# lin_usb_probe.net
KiCad netlist of a schematic drawn in EAGLE
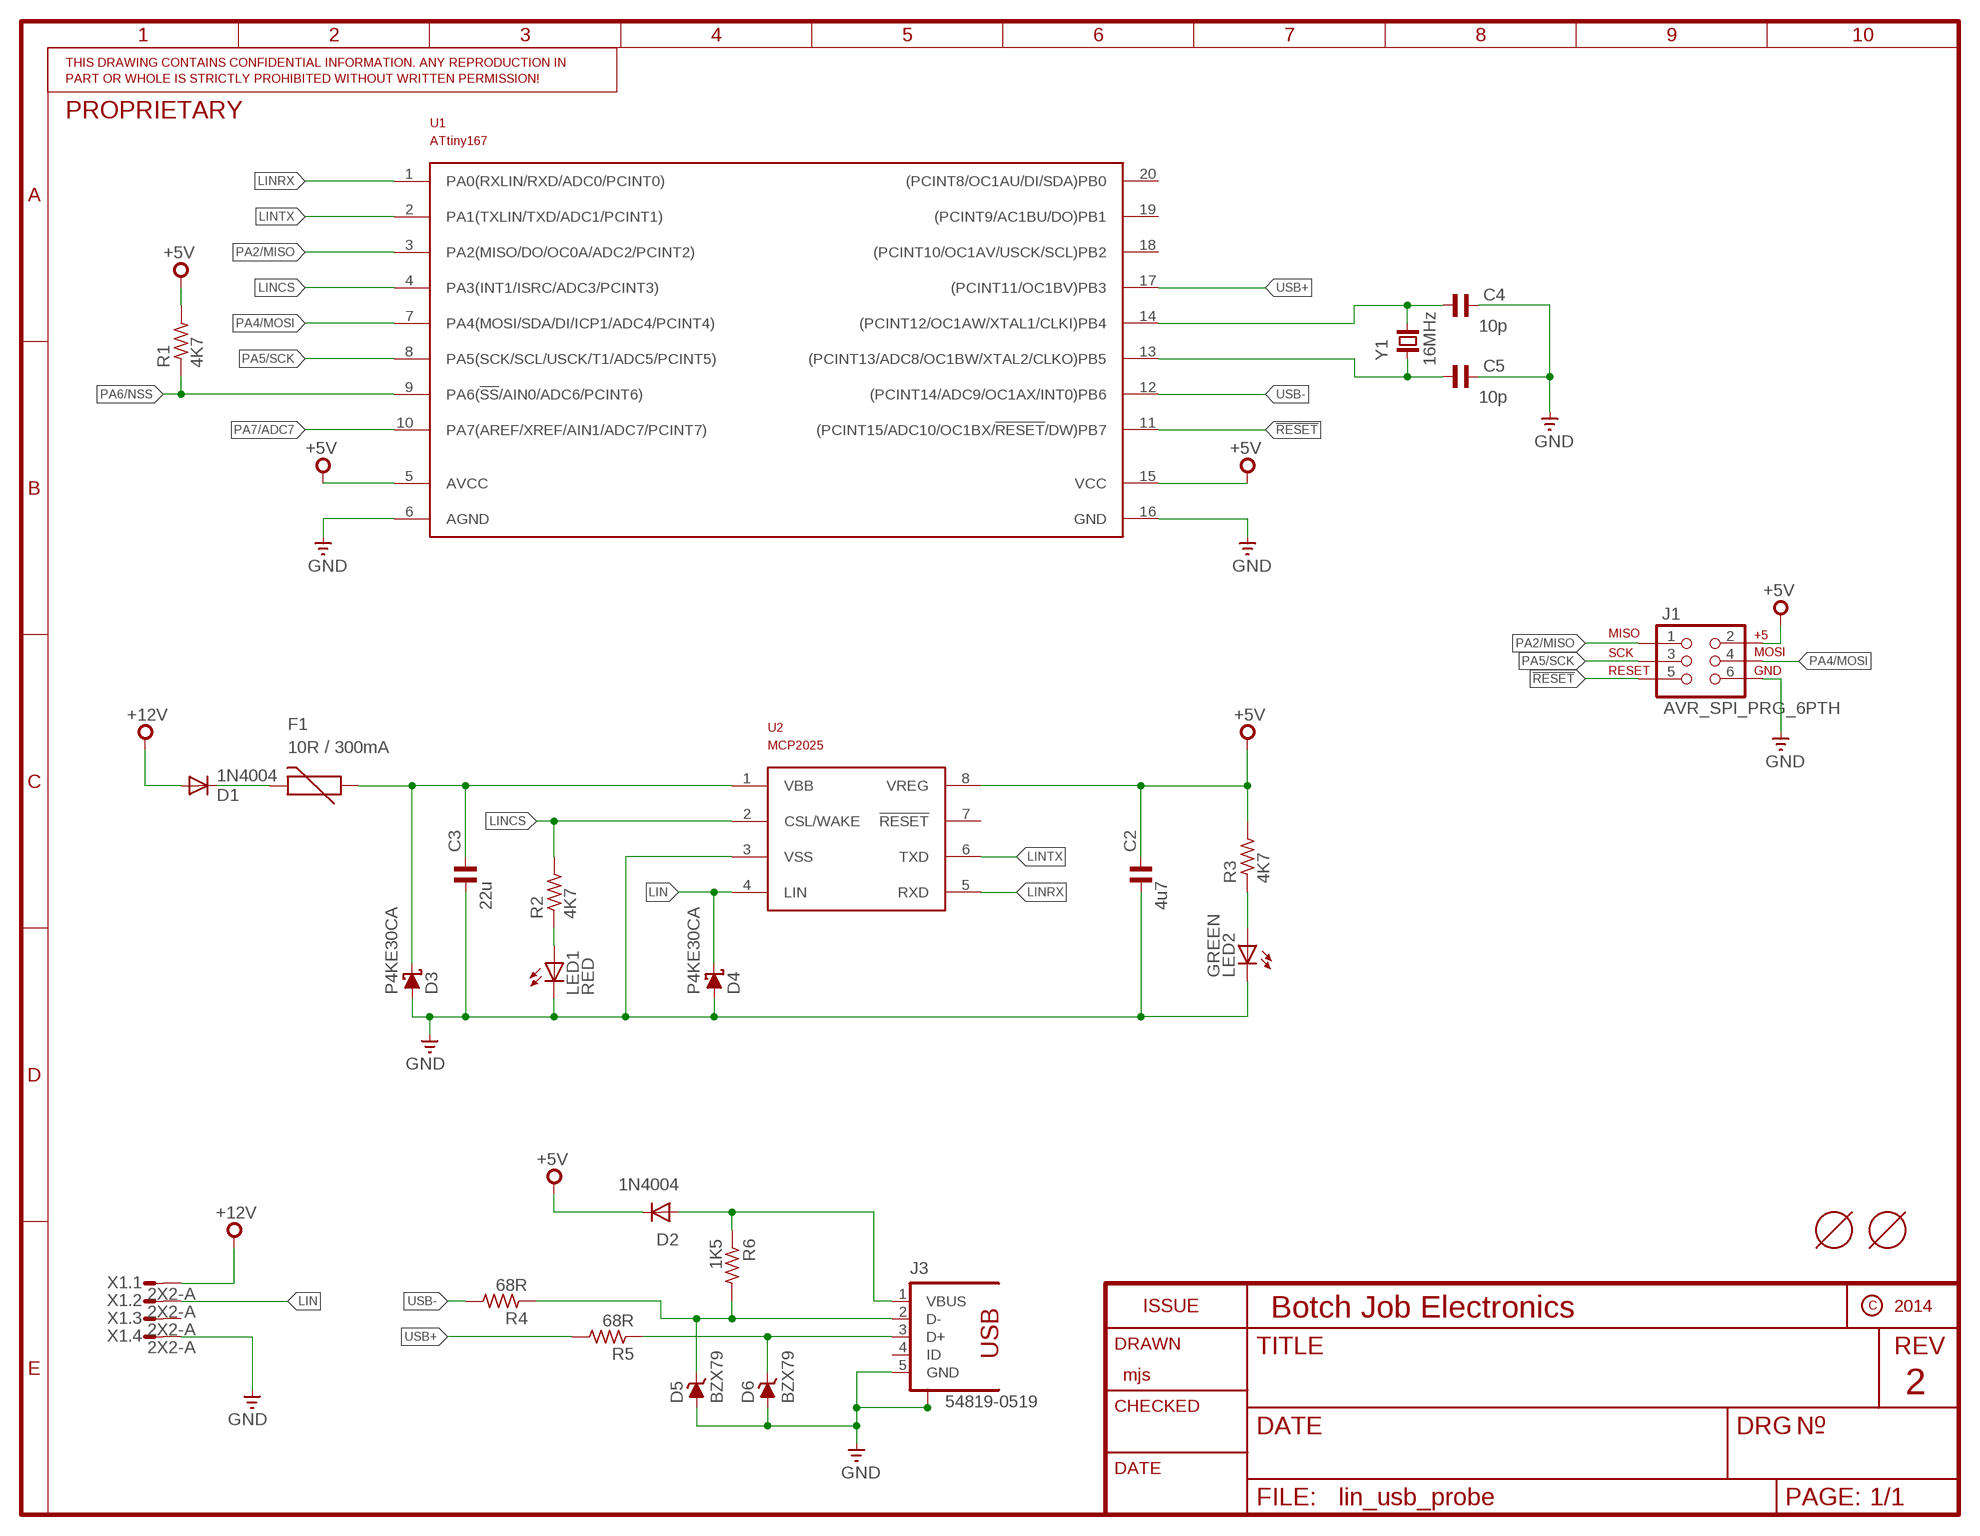
[diagram p0: schematic, sheet 1]

(export (version "E")
  (design (tool "Eeschema 10.0.6"))
  (components
    (comp (ref "C2")
      (value "4u7")
      (footprint "eagle-import:C050-024X044")
      (fields (field (name "PARTNO") "GRM21BR71A475KA73K"))
      (libsource (lib "eagle-import") (part "C-EU050-024X044"))
    )
    (comp (ref "C3")
      (value "22u")
      (footprint "eagle-import:C050-024X044")
      (fields (field (name "PARTNO") "C2012X5R1V226M125AC"))
      (libsource (lib "eagle-import") (part "C-EU050-024X044"))
    )
    (comp (ref "C4")
      (value "10p")
      (footprint "eagle-import:C025-024X044")
      (libsource (lib "eagle-import") (part "C-EU025-024X044"))
    )
    (comp (ref "C5")
      (value "10p")
      (footprint "eagle-import:C025-024X044")
      (libsource (lib "eagle-import") (part "C-EU025-024X044"))
    )
    (comp (ref "D1")
      (value "1N4004")
      (footprint "eagle-import:DO41-10")
      (fields (field (name "PARTNO") "1N4004-TP"))
      (libsource (lib "eagle-import") (part "1N4004"))
    )
    (comp (ref "D2")
      (value "1N4004")
      (footprint "eagle-import:DO41-10")
      (libsource (lib "eagle-import") (part "1N4004"))
    )
    (comp (ref "D3")
      (value "P4KE30CA")
      (footprint "eagle-import:DO41-10")
      (libsource (lib "eagle-import") (part "SCHOTTKY-DIODEDO41-10"))
    )
    (comp (ref "D4")
      (value "P4KE30CA")
      (footprint "eagle-import:DO41-10")
      (libsource (lib "eagle-import") (part "SCHOTTKY-DIODEDO41-10"))
    )
    (comp (ref "D5")
      (value "BZX79")
      (footprint "eagle-import:DO35Z10")
      (libsource (lib "eagle-import") (part "BZX79"))
    )
    (comp (ref "D6")
      (value "BZX79")
      (footprint "eagle-import:DO35Z10")
      (libsource (lib "eagle-import") (part "BZX79"))
    )
    (comp (ref "F1")
      (value "10R / 300mA")
      (footprint "eagle-import:PTC")
      (fields (field (name "PARTNO") "600R150-RBZR"))
      (libsource (lib "eagle-import") (part "PTCPTH"))
    )
    (comp (ref "J1")
      (value "AVR_SPI_PRG_6PTH")
      (footprint "eagle-import:2X3")
      (libsource (lib "eagle-import") (part "AVR_SPI_PRG_6PTH"))
    )
    (comp (ref "J3")
      (value "54819-0519")
      (footprint "eagle-import:54819-0519")
      (libsource (lib "eagle-import") (part "54819-0519"))
    )
    (comp (ref "LED1")
      (value "RED")
      (footprint "eagle-import:LED3MM")
      (fields (field (name "PARTNO") "C4SMF-RJS-CT0W0BB2"))
      (libsource (lib "eagle-import") (part "LED3MM"))
    )
    (comp (ref "LED2")
      (value "GREEN")
      (footprint "eagle-import:LED3MM")
      (fields (field (name "PARTNO") "C4SMF-GJS-CV0Y0792"))
      (libsource (lib "eagle-import") (part "LED3MM"))
    )
    (comp (ref "R1")
      (value "4K7")
      (footprint "eagle-import:0207_10")
      (fields (field (name "PARTNO") "ERJ-6GEYJ472V"))
      (libsource (lib "eagle-import") (part "R-EU_0207/10"))
    )
    (comp (ref "R2")
      (value "4K7")
      (footprint "eagle-import:0207_10")
      (fields (field (name "PARTNO") "ERJ-6GEYJ472V"))
      (libsource (lib "eagle-import") (part "R-EU_0207/10"))
    )
    (comp (ref "R3")
      (value "4K7")
      (footprint "eagle-import:0207_10")
      (fields (field (name "PARTNO") "ERJ-6GEYJ472V"))
      (libsource (lib "eagle-import") (part "R-EU_0207/10"))
    )
    (comp (ref "R4")
      (value "68R")
      (footprint "eagle-import:0207_10")
      (fields (field (name "PARTNO") "ERJ-6GEYJ472V"))
      (libsource (lib "eagle-import") (part "R-EU_0207/10"))
    )
    (comp (ref "R5")
      (value "68R")
      (footprint "eagle-import:0207_10")
      (fields (field (name "PARTNO") "ERJ-6GEYJ472V"))
      (libsource (lib "eagle-import") (part "R-EU_0207/10"))
    )
    (comp (ref "R6")
      (value "1K5")
      (footprint "eagle-import:0207_10")
      (fields (field (name "PARTNO") "ERJ-6GEYJ472V"))
      (libsource (lib "eagle-import") (part "R-EU_0207/10"))
    )
    (comp (ref "U$1")
      (value "MOUNT-HOLE3.1MM")
      (footprint "eagle-import:MOUNT-HOLE3.1")
      (libsource (lib "eagle-import") (part "MOUNT-HOLE3.1MM"))
    )
    (comp (ref "U$2")
      (value "MOUNT-HOLE3.1MM")
      (footprint "eagle-import:MOUNT-HOLE3.1")
      (libsource (lib "eagle-import") (part "MOUNT-HOLE3.1MM"))
    )
    (comp (ref "U1")
      (value "ATtiny167")
      (footprint "eagle-import:TSSOP20")
      (fields (field (name "PARTNO") "ATTINY167-A15XZ"))
      (libsource (lib "eagle-import") (part "ATTINY16720X"))
    )
    (comp (ref "U2")
      (value "MCP2025")
      (footprint "eagle-import:SO08")
      (fields (field (name "PARTNO") "MCP2025-500E/SN"))
      (libsource (lib "eagle-import") (part "MCP2025"))
    )
    (comp (ref "X1")
      (value "2X2-A")
      (footprint "eagle-import:3-794618-4")
      (libsource (lib "eagle-import") (part "2X2-A"))
    )
    (comp (ref "Y1")
      (value "16MHz")
      (footprint "eagle-import:HC49_S")
      (libsource (lib "eagle-import") (part "CRYTALHC49S"))
    )
  )
  (nets
    (net (code "1") (name "+5V") (class "Default")
      (node (ref "C2") (pin "1") (pinfunction "1_1") (pintype "passive"))
      (node (ref "D2") (pin "C") (pinfunction "C_C") (pintype "passive"))
      (node (ref "J1") (pin "2") (pinfunction "2_2") (pintype "passive"))
      (node (ref "R1") (pin "2") (pinfunction "2_2") (pintype "passive"))
      (node (ref "R3") (pin "2") (pinfunction "2_2") (pintype "passive"))
      (node (ref "U1") (pin "15") (pinfunction "VCC_15") (pintype "power_in"))
      (node (ref "U1") (pin "5") (pinfunction "AVCC_5") (pintype "power_in"))
      (node (ref "U2") (pin "8") (pinfunction "VREG_8") (pintype "power_in"))
    )
    (net (code "2") (name "+12V") (class "Default")
      (node (ref "D1") (pin "A") (pinfunction "A_A") (pintype "passive"))
      (node (ref "X1") (pin "1") (pinfunction "S_1") (pintype "passive"))
    )
    (net (code "3") (name "/~{RESET}") (class "Default")
      (node (ref "J1") (pin "5") (pinfunction "5_5") (pintype "passive"))
      (node (ref "U1") (pin "11") (pinfunction "(PCINT15/ADC10/OC1BX/~{RESET}/DW)PB7_11") (pintype "bidirectional"))
    )
    (net (code "4") (name "GND") (class "Default")
      (node (ref "C2") (pin "2") (pinfunction "2_2") (pintype "passive"))
      (node (ref "C3") (pin "2") (pinfunction "2_2") (pintype "passive"))
      (node (ref "C4") (pin "1") (pinfunction "1_1") (pintype "passive"))
      (node (ref "C5") (pin "1") (pinfunction "1_1") (pintype "passive"))
      (node (ref "D3") (pin "A") (pinfunction "A_A") (pintype "passive"))
      (node (ref "D4") (pin "A") (pinfunction "A_A") (pintype "passive"))
      (node (ref "D5") (pin "A") (pinfunction "A_A") (pintype "passive"))
      (node (ref "D6") (pin "A") (pinfunction "A_A") (pintype "passive"))
      (node (ref "J1") (pin "6") (pinfunction "6_6") (pintype "passive"))
      (node (ref "J3") (pin "5") (pinfunction "GND_5") (pintype "passive"))
      (node (ref "J3") (pin "S1") (pinfunction "S1_S1") (pintype "passive"))
      (node (ref "J3") (pin "S2") (pinfunction "S2_S2") (pintype "passive"))
      (node (ref "LED1") (pin "K") (pinfunction "C_K") (pintype "passive"))
      (node (ref "LED2") (pin "K") (pinfunction "C_K") (pintype "passive"))
      (node (ref "U1") (pin "16") (pinfunction "GND_16") (pintype "power_in"))
      (node (ref "U1") (pin "6") (pinfunction "AGND_6") (pintype "power_in"))
      (node (ref "U2") (pin "3") (pinfunction "VSS_3") (pintype "power_in"))
      (node (ref "X1") (pin "4") (pinfunction "S_4") (pintype "passive"))
    )
    (net (code "5") (name "LIN") (class "Default")
      (node (ref "D4") (pin "C") (pinfunction "C_C") (pintype "passive"))
      (node (ref "U2") (pin "4") (pinfunction "LIN_4") (pintype "bidirectional"))
      (node (ref "X1") (pin "2") (pinfunction "S_2") (pintype "passive"))
    )
    (net (code "6") (name "LINCS") (class "Default")
      (node (ref "R2") (pin "2") (pinfunction "2_2") (pintype "passive"))
      (node (ref "U1") (pin "4") (pinfunction "PA3(INT1/ISRC/ADC3/PCINT3)_4") (pintype "bidirectional"))
      (node (ref "U2") (pin "2") (pinfunction "CSL/WAKE_2") (pintype "input"))
    )
    (net (code "7") (name "LINRX") (class "Default")
      (node (ref "U1") (pin "1") (pinfunction "PA0(RXLIN/RXD/ADC0/PCINT0)_1") (pintype "bidirectional"))
      (node (ref "U2") (pin "5") (pinfunction "RXD_5") (pintype "output"))
    )
    (net (code "8") (name "LINTX") (class "Default")
      (node (ref "U1") (pin "2") (pinfunction "PA1(TXLIN/TXD/ADC1/PCINT1)_2") (pintype "bidirectional"))
      (node (ref "U2") (pin "6") (pinfunction "TXD_6") (pintype "input"))
    )
    (net (code "9") (name "Net-(F1-1)") (class "Default")
      (node (ref "C3") (pin "1") (pinfunction "1_1") (pintype "passive"))
      (node (ref "D3") (pin "C") (pinfunction "C_C") (pintype "passive"))
      (node (ref "F1") (pin "P$1") (pinfunction "1_P$1") (pintype "bidirectional"))
      (node (ref "U2") (pin "1") (pinfunction "VBB_1") (pintype "power_in"))
    )
    (net (code "10") (name "Net-(F1-2)") (class "Default")
      (node (ref "D1") (pin "C") (pinfunction "C_C") (pintype "passive"))
      (node (ref "F1") (pin "P$2") (pinfunction "2_P$2") (pintype "bidirectional"))
    )
    (net (code "11") (name "Net-(J3-D+)") (class "Default")
      (node (ref "D6") (pin "C") (pinfunction "C_C") (pintype "passive"))
      (node (ref "J3") (pin "3") (pinfunction "D+_3") (pintype "passive"))
      (node (ref "R5") (pin "1") (pinfunction "1_1") (pintype "passive"))
    )
    (net (code "12") (name "Net-(J3-D-)") (class "Default")
      (node (ref "D5") (pin "C") (pinfunction "C_C") (pintype "passive"))
      (node (ref "J3") (pin "2") (pinfunction "D-_2") (pintype "passive"))
      (node (ref "R4") (pin "1") (pinfunction "1_1") (pintype "passive"))
      (node (ref "R6") (pin "2") (pinfunction "2_2") (pintype "passive"))
    )
    (net (code "13") (name "Net-(J3-VBUS)") (class "Default")
      (node (ref "D2") (pin "A") (pinfunction "A_A") (pintype "passive"))
      (node (ref "J3") (pin "1") (pinfunction "VBUS_1") (pintype "passive"))
      (node (ref "R6") (pin "1") (pinfunction "1_1") (pintype "passive"))
    )
    (net (code "14") (name "Net-(LED1-PadA)") (class "Default")
      (node (ref "LED1") (pin "A") (pinfunction "A_A") (pintype "passive"))
      (node (ref "R2") (pin "1") (pinfunction "1_1") (pintype "passive"))
    )
    (net (code "15") (name "Net-(LED2-PadA)") (class "Default")
      (node (ref "LED2") (pin "A") (pinfunction "A_A") (pintype "passive"))
      (node (ref "R3") (pin "1") (pinfunction "1_1") (pintype "passive"))
    )
    (net (code "16") (name "Net-(U1-(PCINT12{slash}OC1AW{slash}XTAL1{slash}CLKI)PB4)") (class "Default")
      (node (ref "C4") (pin "2") (pinfunction "2_2") (pintype "passive"))
      (node (ref "U1") (pin "14") (pinfunction "(PCINT12/OC1AW/XTAL1/CLKI)PB4_14") (pintype "bidirectional"))
      (node (ref "Y1") (pin "2") (pinfunction "2_2") (pintype "passive"))
    )
    (net (code "17") (name "Net-(U1-(PCINT13{slash}ADC8{slash}OC1BW{slash}XTAL2{slash}CLKO)PB5)") (class "Default")
      (node (ref "C5") (pin "2") (pinfunction "2_2") (pintype "passive"))
      (node (ref "U1") (pin "13") (pinfunction "(PCINT13/ADC8/OC1BW/XTAL2/CLKO)PB5_13") (pintype "bidirectional"))
      (node (ref "Y1") (pin "1") (pinfunction "1_1") (pintype "passive"))
    )
    (net (code "18") (name "PA2{slash}MISO") (class "Default")
      (node (ref "J1") (pin "1") (pinfunction "1_1") (pintype "passive"))
      (node (ref "U1") (pin "3") (pinfunction "PA2(MISO/DO/OC0A/ADC2/PCINT2)_3") (pintype "bidirectional"))
    )
    (net (code "19") (name "PA4{slash}MOSI") (class "Default")
      (node (ref "J1") (pin "4") (pinfunction "4_4") (pintype "passive"))
      (node (ref "U1") (pin "7") (pinfunction "PA4(MOSI/SDA/DI/ICP1/ADC4/PCINT4)_7") (pintype "bidirectional"))
    )
    (net (code "20") (name "PA5{slash}SCK") (class "Default")
      (node (ref "J1") (pin "3") (pinfunction "3_3") (pintype "passive"))
      (node (ref "U1") (pin "8") (pinfunction "PA5(SCK/SCL/USCK/T1/ADC5/PCINT5)_8") (pintype "bidirectional"))
    )
    (net (code "21") (name "PA6{slash}NSS") (class "Default")
      (node (ref "R1") (pin "1") (pinfunction "1_1") (pintype "passive"))
      (node (ref "U1") (pin "9") (pinfunction "PA6(~{SS}/AIN0/ADC6/PCINT6)_9") (pintype "bidirectional"))
    )
    (net (code "22") (name "PA7{slash}ADC7") (class "Default")
      (node (ref "U1") (pin "10") (pinfunction "PA7(AREF/XREF/AIN1/ADC7/PCINT7)_10") (pintype "bidirectional"))
    )
    (net (code "23") (name "USB+") (class "Default")
      (node (ref "R5") (pin "2") (pinfunction "2_2") (pintype "passive"))
      (node (ref "U1") (pin "17") (pinfunction "(PCINT11/OC1BV)PB3_17") (pintype "bidirectional"))
    )
    (net (code "24") (name "USB-") (class "Default")
      (node (ref "R4") (pin "2") (pinfunction "2_2") (pintype "passive"))
      (node (ref "U1") (pin "12") (pinfunction "(PCINT14/ADC9/OC1AX/INT0)PB6_12") (pintype "bidirectional"))
    )
    (net (code "25") (name "unconnected-(J3-ID-Pad4)") (class "Default")
      (node (ref "J3") (pin "4") (pinfunction "ID_4") (pintype "passive"))
    )
    (net (code "26") (name "unconnected-(U1-(PCINT8{slash}OC1AU{slash}DI{slash}SDA)PB0-Pad20)") (class "Default")
      (node (ref "U1") (pin "20") (pinfunction "(PCINT8/OC1AU/DI/SDA)PB0_20") (pintype "bidirectional"))
    )
    (net (code "27") (name "unconnected-(U1-(PCINT9{slash}AC1BU{slash}DO)PB1-Pad19)") (class "Default")
      (node (ref "U1") (pin "19") (pinfunction "(PCINT9/AC1BU/DO)PB1_19") (pintype "bidirectional"))
    )
    (net (code "28") (name "unconnected-(U1-(PCINT10{slash}OC1AV{slash}USCK{slash}SCL)PB2-Pad18)") (class "Default")
      (node (ref "U1") (pin "18") (pinfunction "(PCINT10/OC1AV/USCK/SCL)PB2_18") (pintype "bidirectional"))
    )
    (net (code "29") (name "unconnected-(U2-~{RESET}-Pad7)") (class "Default")
      (node (ref "U2") (pin "7") (pinfunction "~{RESET}_7") (pintype "open_collector"))
    )
    (net (code "30") (name "unconnected-(X1C-S-Pad3)") (class "Default")
      (node (ref "X1") (pin "3") (pinfunction "S_3") (pintype "passive"))
    )
  )
)
